# Sheet1.net
KiCad netlist of a schematic drawn in Altium Designer
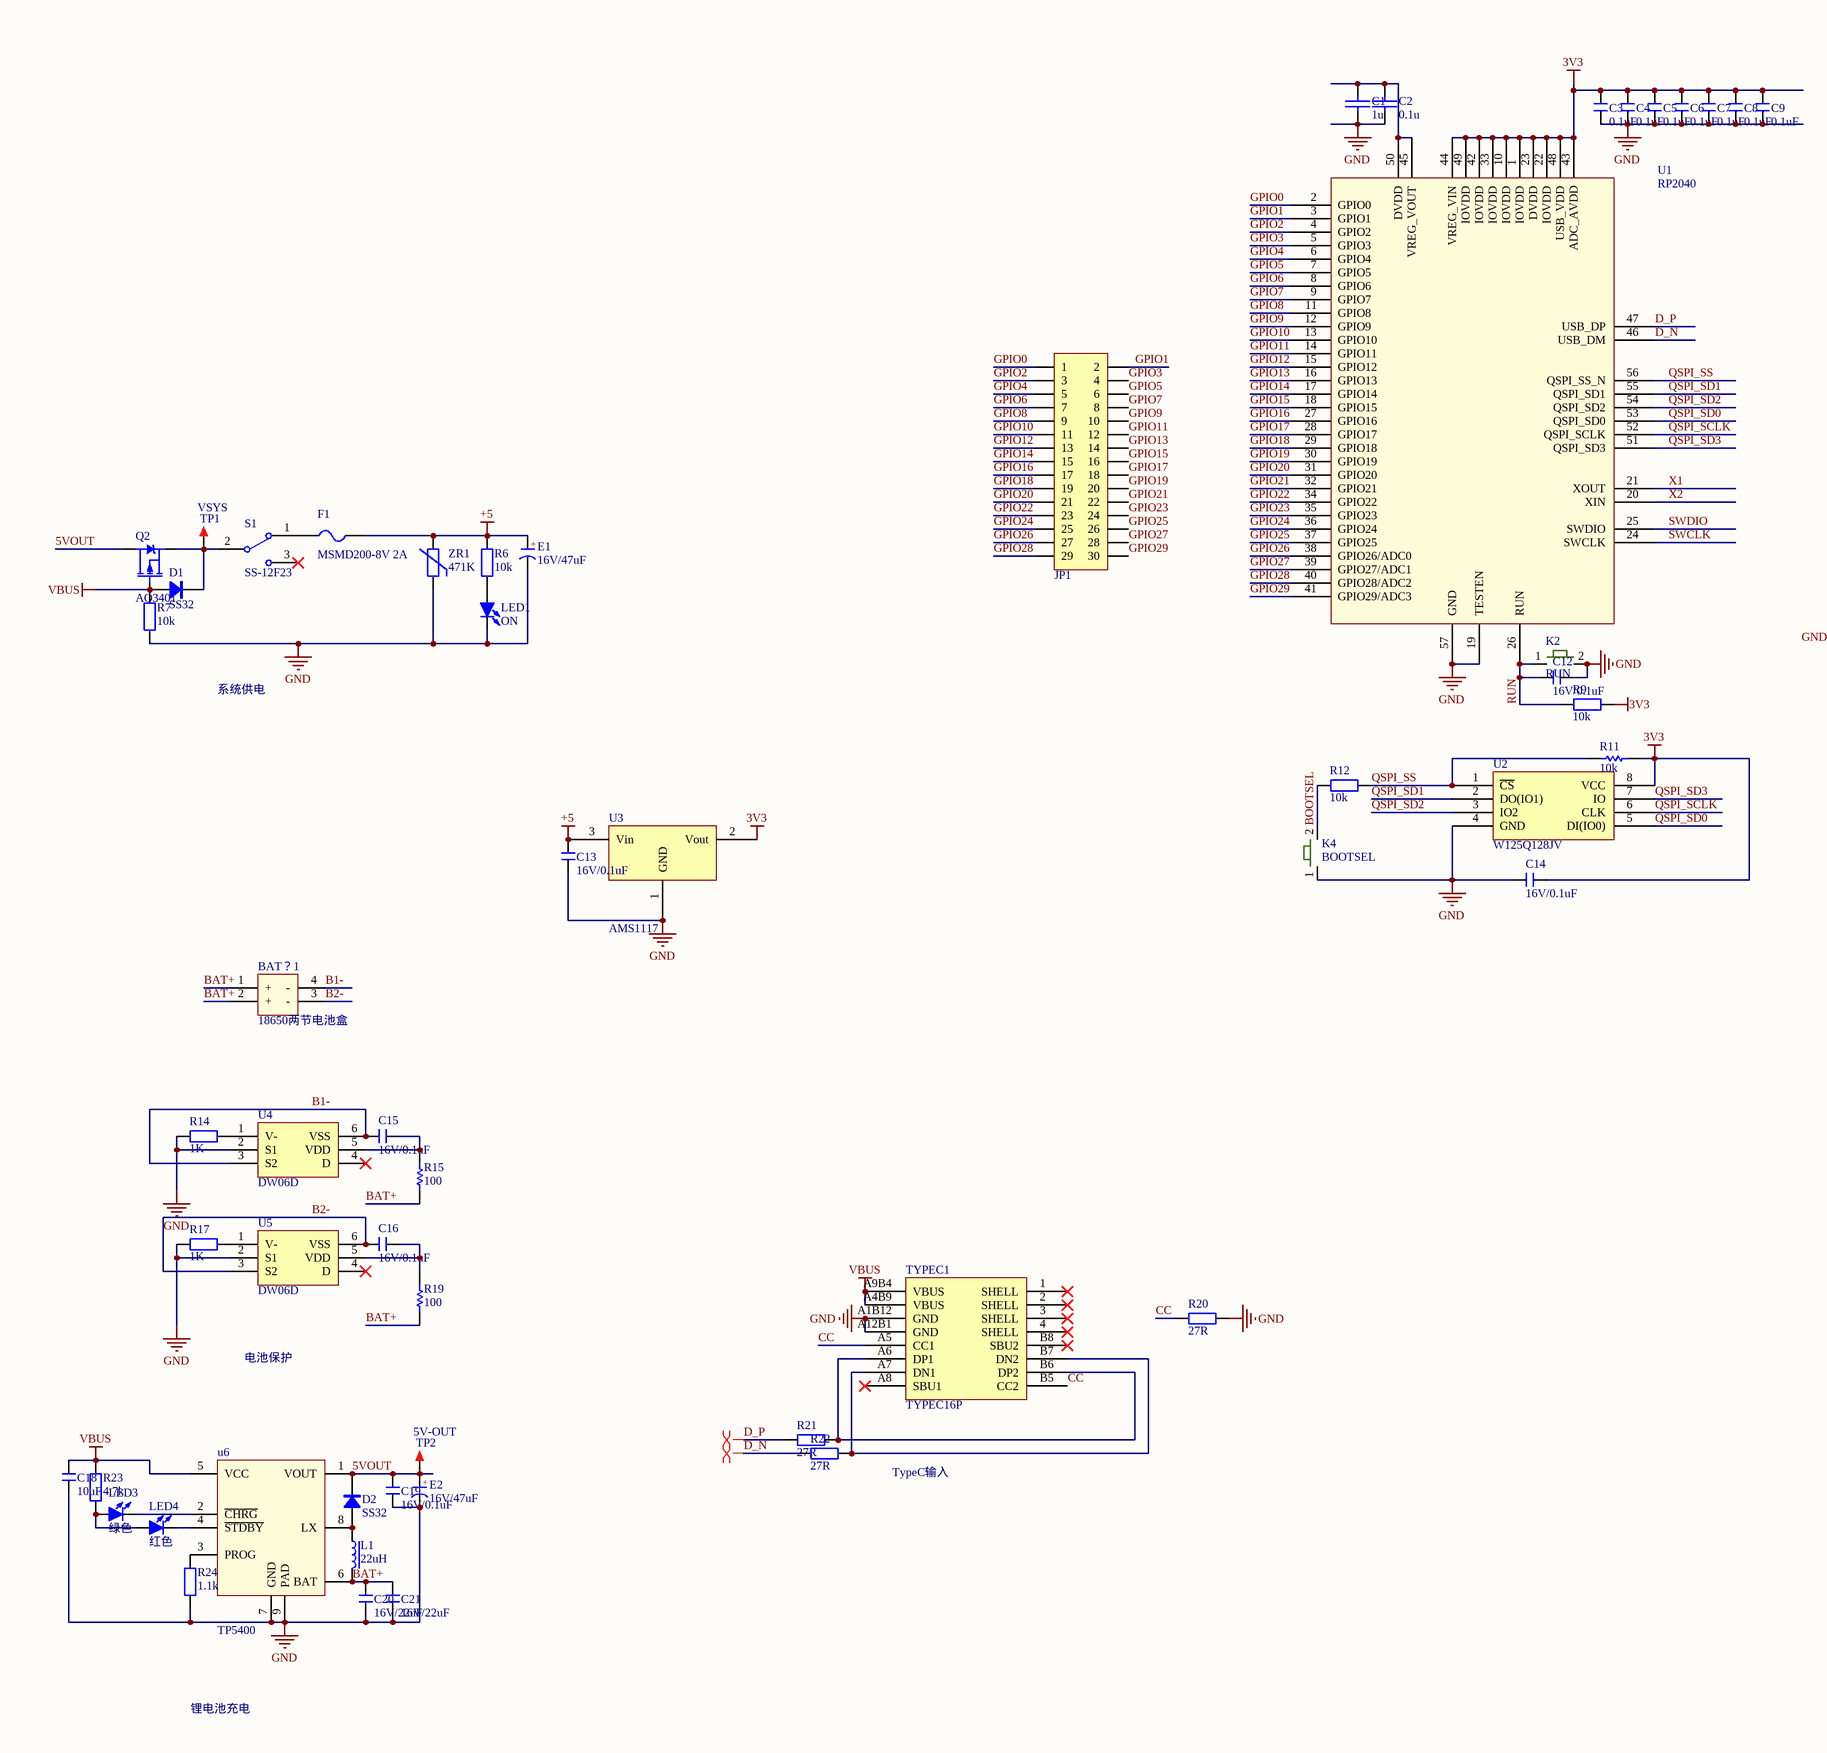
[diagram p0: Sheet1.SchDoc, left]
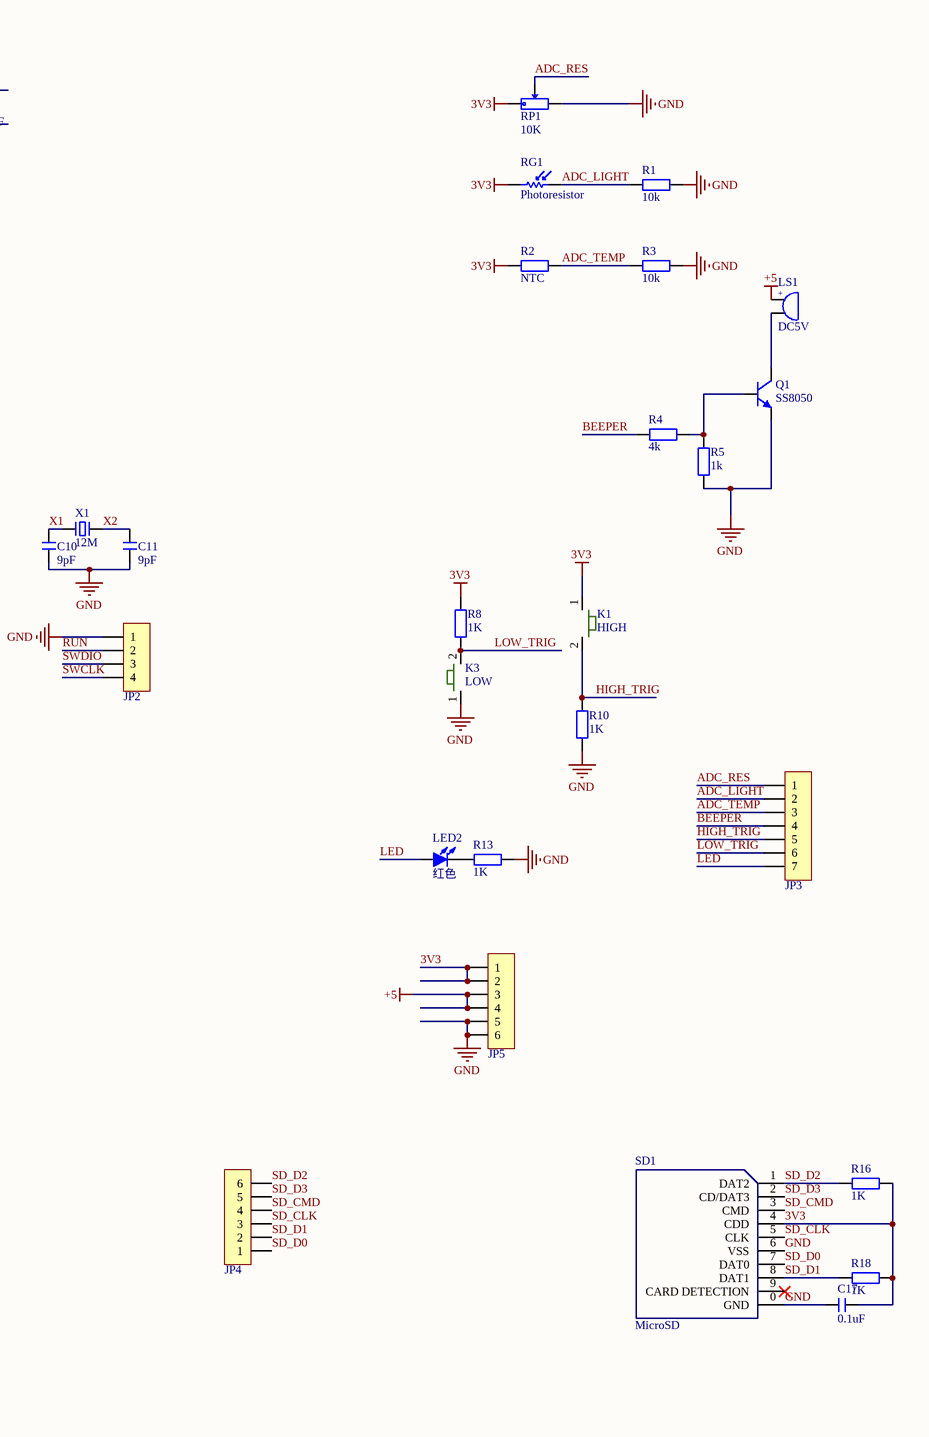
[diagram p1: Sheet1.SchDoc, right]

(export (version "E")
  (design (tool "Eeschema 10.0.6"))
  (components
    (comp (ref "BAT？1")
      (value "18650两节电池盒")
      (footprint "18650两节电池盒")
      (libsource (lib "Schlib1") (part "18650两节电池盒"))
    )
    (comp (ref "C1")
      (value "1u")
      (footprint "C 0603_L")
      (description "靠近RP2040")
      (libsource (lib "电容") (part "CAP"))
    )
    (comp (ref "C2")
      (value "0.1u")
      (footprint "C 0603_L")
      (description "无极性电容")
      (libsource (lib "电容") (part "CAP"))
    )
    (comp (ref "C3")
      (value "0.1uF")
      (footprint "C 0603_L")
      (description "无极性贴片电容")
      (fields (field (name "版权归属") "源创客"))
      (libsource (lib "3.1   - 电阻-电容-电感") (part "C"))
    )
    (comp (ref "C4")
      (value "0.1uF")
      (footprint "C 0603_L")
      (description "无极性贴片电容")
      (fields (field (name "版权归属") "源创客"))
      (libsource (lib "3.1   - 电阻-电容-电感") (part "C"))
    )
    (comp (ref "C5")
      (value "0.1uF")
      (footprint "C 0603_L")
      (description "无极性贴片电容")
      (fields (field (name "版权归属") "源创客"))
      (libsource (lib "3.1   - 电阻-电容-电感") (part "C"))
    )
    (comp (ref "C6")
      (value "0.1uF")
      (footprint "C 0603_L")
      (description "无极性贴片电容")
      (fields (field (name "版权归属") "源创客"))
      (libsource (lib "3.1   - 电阻-电容-电感") (part "C"))
    )
    (comp (ref "C7")
      (value "0.1uF")
      (footprint "C 0603_L")
      (description "无极性贴片电容")
      (fields (field (name "版权归属") "源创客"))
      (libsource (lib "3.1   - 电阻-电容-电感") (part "C"))
    )
    (comp (ref "C8")
      (value "0.1uF")
      (footprint "C 0603_L")
      (description "无极性贴片电容")
      (fields (field (name "版权归属") "源创客"))
      (libsource (lib "3.1   - 电阻-电容-电感") (part "C"))
    )
    (comp (ref "C9")
      (value "0.1uF")
      (footprint "C 0603_L")
      (description "无极性贴片电容")
      (fields (field (name "版权归属") "源创客"))
      (libsource (lib "3.1   - 电阻-电容-电感") (part "C"))
    )
    (comp (ref "C10")
      (value "9pF")
      (footprint "C 0603_L")
      (description "无极性贴片电容")
      (fields (field (name "版权归属") "源创客"))
      (libsource (lib "3.1   - 电阻-电容-电感") (part "C"))
    )
    (comp (ref "C11")
      (value "9pF")
      (footprint "C 0603_L")
      (description "无极性贴片电容")
      (fields (field (name "版权归属") "源创客"))
      (libsource (lib "3.1   - 电阻-电容-电感") (part "C"))
    )
    (comp (ref "C12")
      (value "16V/0.1uF")
      (footprint "C 0603_L")
      (description "无极性贴片电容")
      (fields (field (name "版权归属") "源创客"))
      (libsource (lib "3.1   - 电阻-电容-电感") (part "C"))
    )
    (comp (ref "C13")
      (value "16V/0.1uF")
      (footprint "C 0603_L")
      (description "无极性贴片电容")
      (fields (field (name "版权归属") "源创客"))
      (libsource (lib "3.1   - 电阻-电容-电感") (part "C"))
    )
    (comp (ref "C14")
      (value "16V/0.1uF")
      (footprint "C 0603_L")
      (description "无极性贴片电容")
      (fields (field (name "版权归属") "源创客"))
      (libsource (lib "3.1   - 电阻-电容-电感") (part "C"))
    )
    (comp (ref "C15")
      (value "16V/0.1uF")
      (footprint "C 0603_L")
      (description "无极性贴片电容")
      (fields (field (name "版权归属") "源创客"))
      (libsource (lib "3.1   - 电阻-电容-电感") (part "C"))
    )
    (comp (ref "C16")
      (value "16V/0.1uF")
      (footprint "C 0603_L")
      (description "无极性贴片电容")
      (fields (field (name "版权归属") "源创客"))
      (libsource (lib "3.1   - 电阻-电容-电感") (part "C"))
    )
    (comp (ref "C17")
      (value "0.1uF")
      (footprint "C 0603_L")
      (description "无极性贴片电容")
      (fields (field (name "版权归属") "源创客"))
      (libsource (lib "3.1   - 电阻-电容-电感") (part "C"))
    )
    (comp (ref "C18")
      (value "10uF")
      (footprint "C 0603_L")
      (description "无极性贴片电容")
      (fields (field (name "版权归属") "源创客"))
      (libsource (lib "3.1   - 电阻-电容-电感") (part "C"))
    )
    (comp (ref "C19")
      (value "16V/0.1uF")
      (footprint "C 0603_L")
      (description "无极性贴片电容")
      (fields (field (name "版权归属") "源创客"))
      (libsource (lib "3.1   - 电阻-电容-电感") (part "C"))
    )
    (comp (ref "C20")
      (value "16V/22uF")
      (footprint "C 0603_L")
      (description "无极性贴片电容")
      (fields (field (name "版权归属") "源创客"))
      (libsource (lib "3.1   - 电阻-电容-电感") (part "C"))
    )
    (comp (ref "C21")
      (value "16V/22uF")
      (footprint "C 0603_L")
      (description "无极性贴片电容")
      (fields (field (name "版权归属") "源创客"))
      (libsource (lib "3.1   - 电阻-电容-电感") (part "C"))
    )
    (comp (ref "D1")
      (value "SS32")
      (footprint "SMA")
      (description "肖特基二极管")
      (fields (field (name "版权归属") "源创客"))
      (libsource (lib "8.1   - 二极管-整流桥") (part "SS210"))
    )
    (comp (ref "D2")
      (value "SS32")
      (footprint "SMA")
      (description "肖特基二极管")
      (fields (field (name "版权归属") "源创客"))
      (libsource (lib "8.1   - 二极管-整流桥") (part "SS210"))
    )
    (comp (ref "E1")
      (value "16V/47uF")
      (footprint "CM C(5*5.4)")
      (description "贴片电解电容")
      (fields (field (name "版权归属") "源创客"))
      (libsource (lib "3.1   - 电阻-电容-电感") (part "C-CM"))
    )
    (comp (ref "E2")
      (value "16V/47uF")
      (footprint "CM C(5*5.4)")
      (description "贴片电解电容")
      (fields (field (name "版权归属") "源创客"))
      (libsource (lib "3.1   - 电阻-电容-电感") (part "C-CM"))
    )
    (comp (ref "F1")
      (value "MSMD200-8V 2A")
      (footprint "FU 1206")
      (description "贴片保险丝")
      (fields (field (name "版权归属") "源创客"))
      (libsource (lib "10.1 - 保险丝-晶振") (part "FU"))
    )
    (comp (ref "JP1")
      (value "Header 2X11")
      (footprint "HDR2.54-LI-2x15P")
      (description "15*2P接插件")
      (fields (field (name "版权归属") "源创客"))
      (libsource (lib "4.6   - 接插件-脚距2.54") (part "Header 15X2"))
    )
    (comp (ref "JP2")
      (value "DEBUG")
      (footprint "HDR2.54-LI-4P")
      (description "4P接插件")
      (fields (field (name "版权归属") "源创客"))
      (libsource (lib "4.6   - 接插件-脚距2.54") (part "Header 4"))
    )
    (comp (ref "JP3")
      (value "HDR-1X7")
      (footprint "HDR2.54-LI-7P")
      (description "7P接插件")
      (fields (field (name "版权归属") "源创客"))
      (libsource (lib "4.6   - 接插件-脚距2.54") (part "Header 7"))
    )
    (comp (ref "JP4")
      (value "HDR-1X6")
      (footprint "HDR2.54-LI-6P")
      (description "6P接插件")
      (fields (field (name "版权归属") "源创客"))
      (libsource (lib "") (part "Header 6_1"))
    )
    (comp (ref "JP5")
      (value "HDR-1X6")
      (footprint "HDR2.54-LI-6P")
      (description "6P接插件")
      (fields (field (name "版权归属") "源创客"))
      (libsource (lib "4.6   - 接插件-脚距2.54") (part "Header 6"))
    )
    (comp (ref "K1") (value "HIGH") (footprint "轻触按键") (libsource (lib "Schlib1") (part "两脚轻触开关")))
    (comp (ref "K2") (value "RUN") (footprint "轻触按键") (libsource (lib "Schlib1") (part "两脚轻触开关")))
    (comp (ref "K3") (value "LOW") (footprint "轻触按键") (libsource (lib "Schlib1") (part "两脚轻触开关")))
    (comp (ref "K4") (value "BOOTSEL") (footprint "轻触按键") (libsource (lib "Schlib1") (part "两脚轻触开关")))
    (comp (ref "L1")
      (value "22uH")
      (footprint "NR4020")
      (description "NR磁胶电感")
      (fields (field (name "版权归属") "源创客"))
      (libsource (lib "3.1   - 电阻-电容-电感") (part "L-NR"))
    )
    (comp (ref "LED1")
      (value "ON")
      (footprint "LED 0603R")
      (description "贴片LED")
      (fields (field (name "版权归属") "源创客"))
      (libsource (lib "9.1   - LED") (part "LED-SMD"))
    )
    (comp (ref "LED2")
      (value "红色")
      (footprint "LED 0603R")
      (description "贴片LED")
      (fields (field (name "版权归属") "源创客"))
      (libsource (lib "9.1   - LED") (part "LED-SMD"))
    )
    (comp (ref "LED3")
      (value "绿色")
      (footprint "LED 0603G")
      (description "贴片LED")
      (fields (field (name "版权归属") "源创客"))
      (libsource (lib "9.1   - LED") (part "LED-SMD"))
    )
    (comp (ref "LED4")
      (value "红色")
      (footprint "LED 0603R")
      (description "贴片LED")
      (fields (field (name "版权归属") "源创客"))
      (libsource (lib "9.1   - LED") (part "LED-SMD"))
    )
    (comp (ref "LS1")
      (value "DC5V")
      (footprint "BUZZER-7525")
      (description "蜂鸣器")
      (fields (field (name "版权归属") "源创客"))
      (libsource (lib "15.1 - 未分类器件") (part "BEEP"))
    )
    (comp (ref "Q1")
      (value "SS8050")
      (footprint "SOT-23")
      (description "高频放大-NPN型")
      (fields (field (name "版权归属") "源创客"))
      (libsource (lib "6.2   - 三极管") (part "8050-SMD"))
    )
    (comp (ref "Q2")
      (value "AO3401")
      (footprint "SOT23")
      (description "P沟道场效应管")
      (libsource (lib "MOS管") (part "P-MOS"))
    )
    (comp (ref "R1")
      (value "10k")
      (footprint "R 0603_L")
      (description "贴片电阻")
      (fields (field (name "版权归属") "源创客"))
      (libsource (lib "3.1   - 电阻-电容-电感") (part "R"))
    )
    (comp (ref "R2")
      (value "NTC")
      (footprint "R 0603_L")
      (description "贴片电阻")
      (fields (field (name "版权归属") "源创客"))
      (libsource (lib "3.1   - 电阻-电容-电感") (part "R"))
    )
    (comp (ref "R3")
      (value "10k")
      (footprint "R 0603_L")
      (description "贴片电阻")
      (fields (field (name "版权归属") "源创客"))
      (libsource (lib "3.1   - 电阻-电容-电感") (part "R"))
    )
    (comp (ref "R4")
      (value "4k")
      (footprint "R 0603_L")
      (description "贴片电阻")
      (fields (field (name "版权归属") "源创客"))
      (libsource (lib "3.1   - 电阻-电容-电感") (part "R"))
    )
    (comp (ref "R5")
      (value "1k")
      (footprint "R 0603_L")
      (description "贴片电阻")
      (fields (field (name "版权归属") "源创客"))
      (libsource (lib "3.1   - 电阻-电容-电感") (part "R"))
    )
    (comp (ref "R6")
      (value "10k")
      (footprint "R 0603_L")
      (description "贴片电阻")
      (fields (field (name "版权归属") "源创客"))
      (libsource (lib "3.1   - 电阻-电容-电感") (part "R"))
    )
    (comp (ref "R7")
      (value "10k")
      (footprint "R 0603_L")
      (description "贴片电阻")
      (fields (field (name "版权归属") "源创客"))
      (libsource (lib "3.1   - 电阻-电容-电感") (part "R"))
    )
    (comp (ref "R8")
      (value "1K")
      (footprint "R 0603_L")
      (description "贴片电阻")
      (fields (field (name "版权归属") "源创客"))
      (libsource (lib "3.1   - 电阻-电容-电感") (part "R"))
    )
    (comp (ref "R9")
      (value "10k")
      (footprint "R 0603_L")
      (description "贴片电阻")
      (fields (field (name "版权归属") "源创客"))
      (libsource (lib "3.1   - 电阻-电容-电感") (part "R"))
    )
    (comp (ref "R10")
      (value "1K")
      (footprint "R 0603_L")
      (description "贴片电阻")
      (fields (field (name "版权归属") "源创客"))
      (libsource (lib "3.1   - 电阻-电容-电感") (part "R"))
    )
    (comp (ref "R11") (value "10k") (footprint "R 0603_L") (libsource (lib "电阻") (part "RES")))
    (comp (ref "R12")
      (value "10k")
      (footprint "R 0603_L")
      (description "贴片电阻")
      (fields (field (name "版权归属") "源创客"))
      (libsource (lib "3.1   - 电阻-电容-电感") (part "R"))
    )
    (comp (ref "R13")
      (value "1K")
      (footprint "R 0603_L")
      (description "贴片电阻")
      (fields (field (name "版权归属") "源创客"))
      (libsource (lib "3.1   - 电阻-电容-电感") (part "R"))
    )
    (comp (ref "R14")
      (value "1K")
      (footprint "R 0603_L")
      (description "贴片电阻")
      (fields (field (name "版权归属") "源创客"))
      (libsource (lib "3.1   - 电阻-电容-电感") (part "R"))
    )
    (comp (ref "R15") (value "100") (footprint "R 0603_L") (libsource (lib "电阻") (part "RES")))
    (comp (ref "R16")
      (value "1K")
      (footprint "R 0603_L")
      (description "贴片电阻")
      (fields (field (name "版权归属") "源创客"))
      (libsource (lib "3.1   - 电阻-电容-电感") (part "R"))
    )
    (comp (ref "R17")
      (value "1K")
      (footprint "R 0603_L")
      (description "贴片电阻")
      (fields (field (name "版权归属") "源创客"))
      (libsource (lib "3.1   - 电阻-电容-电感") (part "R"))
    )
    (comp (ref "R18")
      (value "1K")
      (footprint "R 0603_L")
      (description "贴片电阻")
      (fields (field (name "版权归属") "源创客"))
      (libsource (lib "3.1   - 电阻-电容-电感") (part "R"))
    )
    (comp (ref "R19") (value "100") (footprint "R 0603_L") (libsource (lib "电阻") (part "RES")))
    (comp (ref "R20")
      (value "27R")
      (footprint "R 0603_L")
      (description "贴片电阻")
      (fields (field (name "版权归属") "源创客"))
      (libsource (lib "3.1   - 电阻-电容-电感") (part "R"))
    )
    (comp (ref "R21")
      (value "27R")
      (footprint "R 0603_L")
      (description "贴片电阻")
      (fields (field (name "版权归属") "源创客"))
      (libsource (lib "3.1   - 电阻-电容-电感") (part "R"))
    )
    (comp (ref "R22")
      (value "27R")
      (footprint "R 0603_L")
      (description "贴片电阻")
      (fields (field (name "版权归属") "源创客"))
      (libsource (lib "3.1   - 电阻-电容-电感") (part "R"))
    )
    (comp (ref "R23")
      (value "4.7k")
      (footprint "R 0603_L")
      (description "贴片电阻")
      (fields (field (name "版权归属") "源创客"))
      (libsource (lib "3.1   - 电阻-电容-电感") (part "R"))
    )
    (comp (ref "R24")
      (value "1.1k")
      (footprint "R 0603_L")
      (description "贴片电阻")
      (fields (field (name "版权归属") "源创客"))
      (libsource (lib "3.1   - 电阻-电容-电感") (part "R"))
    )
    (comp (ref "RG1")
      (value "Photoresistor")
      (footprint "Photoresistor")
      (description "光敏电阻")
      (libsource (lib "电阻") (part "Photoresistor"))
    )
    (comp (ref "RP1")
      (value "10K")
      (footprint "拨盘电位器")
      (description "贴片电位器")
      (fields (field (name "版权归属") "源创客"))
      (libsource (lib "3.1   - 电阻-电容-电感") (part "RP-SMD"))
    )
    (comp (ref "S1")
      (value "SS-12F23")
      (footprint "SK-12D07VG3")
      (description "1路波动开关")
      (fields (field (name "版权归属") "源创客"))
      (libsource (lib "5.1   - 按键-开关") (part "SSW-1P"))
    )
    (comp (ref "SD1") (value "MicroSD") (footprint "Micro SD") (libsource (lib "SD Card") (part "MicroSD")))
    (comp (ref "TP1")
      (value "VSYS")
      (footprint "TEST 1")
      (description "测试点")
      (fields (field (name "版权归属") "源创客"))
      (libsource (lib "15.1 - 未分类器件") (part "TEST"))
    )
    (comp (ref "TP2")
      (value "5V-OUT")
      (footprint "TEST 1")
      (description "测试点")
      (fields (field (name "版权归属") "源创客"))
      (libsource (lib "15.1 - 未分类器件") (part "TEST"))
    )
    (comp (ref "TYPEC1")
      (value "TYPEC16P")
      (footprint "TYPEC-16P")
      (libsource (lib "Schlib1") (part "TYPEC16P"))
    )
    (comp (ref "U1") (value "RP2040") (footprint "QFN-56") (libsource (lib "Schlib1") (part "RP2040")))
    (comp (ref "U2")
      (value "W125Q128JV")
      (footprint "SOIC-8-208mil")
      (libsource (lib "Schlib1") (part "W125Q128JV"))
    )
    (comp (ref "U3")
      (value "AMS1117")
      (footprint "SOT89")
      (description "三端稳压芯片")
      (libsource (lib "电源芯片") (part "AMS1117"))
    )
    (comp (ref "U4") (value "DW06D") (footprint "SOT23-6") (libsource (lib "Schlib1") (part "DW06D")))
    (comp (ref "U5") (value "DW06D") (footprint "SOT23-6") (libsource (lib "Schlib1") (part "DW06D")))
    (comp (ref "u6") (value "TP5400") (footprint "ESOP8") (libsource (lib "Schlib1") (part "TP5400")))
    (comp (ref "X1")
      (value "12M")
      (footprint "OSC HC-49SMD")
      (description "2脚无源脚晶振")
      (libsource (lib "晶振") (part "XTAL-2P"))
    )
    (comp (ref "ZR1")
      (value "471K")
      (footprint "R 0603_L")
      (description "压敏电阻")
      (fields (field (name "版权归属") "源创客"))
      (libsource (lib "3.1   - 电阻-电容-电感") (part "R_VDR"))
    )
  )
  (nets
    (net (code "1") (name "+5") (class "Default")
      (node (ref "C13") (pin "2") (pinfunction "2_2") (pintype "passive"))
      (node (ref "E1") (pin "1") (pinfunction "A_1") (pintype "passive"))
      (node (ref "F1") (pin "2") (pinfunction "2_2") (pintype "passive"))
      (node (ref "JP5") (pin "3") (pinfunction "3_3") (pintype "passive"))
      (node (ref "JP5") (pin "4") (pinfunction "4_4") (pintype "passive"))
      (node (ref "LS1") (pin "1") (pinfunction "1_1") (pintype "passive"))
      (node (ref "R6") (pin "2") (pinfunction "2_2") (pintype "passive"))
      (node (ref "U3") (pin "3") (pinfunction "Vin_3") (pintype "passive"))
      (node (ref "ZR1") (pin "2") (pinfunction "2_2") (pintype "passive"))
    )
    (net (code "2") (name "/5VOUT") (class "Default")
      (node (ref "C19") (pin "2") (pinfunction "2_2") (pintype "passive"))
      (node (ref "D2") (pin "2") (pinfunction "K_2") (pintype "passive"))
      (node (ref "E2") (pin "1") (pinfunction "A_1") (pintype "passive"))
      (node (ref "Q2") (pin "D") (pinfunction "D_D") (pintype "passive"))
      (node (ref "TP2") (pin "1") (pinfunction "1_1") (pintype "passive"))
      (node (ref "u6") (pin "1") (pinfunction "VOUT_1") (pintype "passive"))
    )
    (net (code "3") (name "/ADC_LIGHT") (class "Default")
      (node (ref "JP3") (pin "2") (pinfunction "2_2") (pintype "passive"))
      (node (ref "R1") (pin "2") (pinfunction "2_2") (pintype "passive"))
      (node (ref "RG1") (pin "2") (pinfunction "2_2") (pintype "passive"))
    )
    (net (code "4") (name "/ADC_RES") (class "Default")
      (node (ref "JP3") (pin "1") (pinfunction "1_1") (pintype "passive"))
      (node (ref "RP1") (pin "2") (pinfunction "2_2") (pintype "passive"))
    )
    (net (code "5") (name "/ADC_TEMP") (class "Default")
      (node (ref "JP3") (pin "3") (pinfunction "3_3") (pintype "passive"))
      (node (ref "R2") (pin "2") (pinfunction "2_2") (pintype "passive"))
      (node (ref "R3") (pin "2") (pinfunction "2_2") (pintype "passive"))
    )
    (net (code "6") (name "/B1-") (class "Default")
      (node (ref "BAT？1") (pin "4") (pinfunction "-_4") (pintype "passive"))
      (node (ref "C15") (pin "2") (pinfunction "2_2") (pintype "passive"))
      (node (ref "U4") (pin "3") (pinfunction "S2_3") (pintype "passive"))
      (node (ref "U4") (pin "6") (pinfunction "VSS_6") (pintype "passive"))
    )
    (net (code "7") (name "/B2-") (class "Default")
      (node (ref "BAT？1") (pin "3") (pinfunction "-_3") (pintype "passive"))
      (node (ref "C16") (pin "2") (pinfunction "2_2") (pintype "passive"))
      (node (ref "U5") (pin "3") (pinfunction "S2_3") (pintype "passive"))
      (node (ref "U5") (pin "6") (pinfunction "VSS_6") (pintype "passive"))
    )
    (net (code "8") (name "/BAT+") (class "Default")
      (node (ref "BAT？1") (pin "1") (pinfunction "+_1") (pintype "passive"))
      (node (ref "BAT？1") (pin "2") (pinfunction "+_2") (pintype "passive"))
      (node (ref "C20") (pin "2") (pinfunction "2_2") (pintype "passive"))
      (node (ref "C21") (pin "2") (pinfunction "2_2") (pintype "passive"))
      (node (ref "L1") (pin "2") (pinfunction "2_2") (pintype "passive"))
      (node (ref "R15") (pin "2") (pinfunction "2_2") (pintype "passive"))
      (node (ref "R19") (pin "2") (pinfunction "2_2") (pintype "passive"))
      (node (ref "u6") (pin "6") (pinfunction "BAT_6") (pintype "passive"))
    )
    (net (code "9") (name "/BEEPER") (class "Default")
      (node (ref "JP3") (pin "4") (pinfunction "4_4") (pintype "passive"))
      (node (ref "R4") (pin "1") (pinfunction "1_1") (pintype "passive"))
    )
    (net (code "10") (name "/BOOTSEL") (class "Default")
      (node (ref "K4") (pin "2") (pintype "passive"))
      (node (ref "R12") (pin "2") (pinfunction "2_2") (pintype "passive"))
    )
    (net (code "11") (name "/CC") (class "Default")
      (node (ref "R20") (pin "1") (pinfunction "1_1") (pintype "passive"))
      (node (ref "TYPEC1") (pin "A5") (pinfunction "CC1_A5") (pintype "passive"))
      (node (ref "TYPEC1") (pin "B5") (pinfunction "CC2_B5") (pintype "passive"))
    )
    (net (code "12") (name "/D_N") (class "Default")
      (node (ref "R22") (pin "1") (pinfunction "1_1") (pintype "passive"))
      (node (ref "U1") (pin "46") (pinfunction "USB_DM_46") (pintype "passive"))
    )
    (net (code "13") (name "/D_P") (class "Default")
      (node (ref "R21") (pin "1") (pinfunction "1_1") (pintype "passive"))
      (node (ref "U1") (pin "47") (pinfunction "USB_DP_47") (pintype "passive"))
    )
    (net (code "14") (name "/GPIO0") (class "Default")
      (node (ref "JP1") (pin "1") (pinfunction "1_1") (pintype "passive"))
      (node (ref "U1") (pin "2") (pinfunction "GPIO0_2") (pintype "passive"))
    )
    (net (code "15") (name "/GPIO1") (class "Default")
      (node (ref "JP1") (pin "2") (pinfunction "2_2") (pintype "passive"))
      (node (ref "U1") (pin "3") (pinfunction "GPIO1_3") (pintype "passive"))
    )
    (net (code "16") (name "/GPIO2") (class "Default")
      (node (ref "JP1") (pin "3") (pinfunction "3_3") (pintype "passive"))
      (node (ref "U1") (pin "4") (pinfunction "GPIO2_4") (pintype "passive"))
    )
    (net (code "17") (name "/GPIO3") (class "Default")
      (node (ref "JP1") (pin "4") (pinfunction "4_4") (pintype "passive"))
      (node (ref "U1") (pin "5") (pinfunction "GPIO3_5") (pintype "passive"))
    )
    (net (code "18") (name "/GPIO4") (class "Default")
      (node (ref "JP1") (pin "5") (pinfunction "5_5") (pintype "passive"))
      (node (ref "U1") (pin "6") (pinfunction "GPIO4_6") (pintype "passive"))
    )
    (net (code "19") (name "/GPIO5") (class "Default")
      (node (ref "JP1") (pin "6") (pinfunction "6_6") (pintype "passive"))
      (node (ref "U1") (pin "7") (pinfunction "GPIO5_7") (pintype "passive"))
    )
    (net (code "20") (name "/GPIO6") (class "Default")
      (node (ref "JP1") (pin "7") (pinfunction "7_7") (pintype "passive"))
      (node (ref "U1") (pin "8") (pinfunction "GPIO6_8") (pintype "passive"))
    )
    (net (code "21") (name "/GPIO7") (class "Default")
      (node (ref "JP1") (pin "8") (pinfunction "8_8") (pintype "passive"))
      (node (ref "U1") (pin "9") (pinfunction "GPIO7_9") (pintype "passive"))
    )
    (net (code "22") (name "/GPIO8") (class "Default")
      (node (ref "JP1") (pin "9") (pinfunction "9_9") (pintype "passive"))
      (node (ref "U1") (pin "11") (pinfunction "GPIO8_11") (pintype "passive"))
    )
    (net (code "23") (name "/GPIO9") (class "Default")
      (node (ref "JP1") (pin "10") (pinfunction "10_10") (pintype "passive"))
      (node (ref "U1") (pin "12") (pinfunction "GPIO9_12") (pintype "passive"))
    )
    (net (code "24") (name "/GPIO10") (class "Default")
      (node (ref "JP1") (pin "11") (pinfunction "11_11") (pintype "passive"))
      (node (ref "U1") (pin "13") (pinfunction "GPIO10_13") (pintype "passive"))
    )
    (net (code "25") (name "/GPIO11") (class "Default")
      (node (ref "JP1") (pin "12") (pinfunction "12_12") (pintype "passive"))
      (node (ref "U1") (pin "14") (pinfunction "GPIO11_14") (pintype "passive"))
    )
    (net (code "26") (name "/GPIO12") (class "Default")
      (node (ref "JP1") (pin "13") (pinfunction "13_13") (pintype "passive"))
      (node (ref "U1") (pin "15") (pinfunction "GPIO12_15") (pintype "passive"))
    )
    (net (code "27") (name "/GPIO13") (class "Default")
      (node (ref "JP1") (pin "14") (pinfunction "14_14") (pintype "passive"))
      (node (ref "U1") (pin "16") (pinfunction "GPIO13_16") (pintype "passive"))
    )
    (net (code "28") (name "/GPIO14") (class "Default")
      (node (ref "JP1") (pin "15") (pinfunction "15_15") (pintype "passive"))
      (node (ref "U1") (pin "17") (pinfunction "GPIO14_17") (pintype "passive"))
    )
    (net (code "29") (name "/GPIO15") (class "Default")
      (node (ref "JP1") (pin "16") (pinfunction "16_16") (pintype "passive"))
      (node (ref "U1") (pin "18") (pinfunction "GPIO15_18") (pintype "passive"))
    )
    (net (code "30") (name "/GPIO16") (class "Default")
      (node (ref "JP1") (pin "17") (pinfunction "17_17") (pintype "passive"))
      (node (ref "U1") (pin "27") (pinfunction "GPIO16_27") (pintype "passive"))
    )
    (net (code "31") (name "/GPIO17") (class "Default")
      (node (ref "JP1") (pin "18") (pinfunction "18_18") (pintype "passive"))
      (node (ref "U1") (pin "28") (pinfunction "GPIO17_28") (pintype "passive"))
    )
    (net (code "32") (name "/GPIO18") (class "Default")
      (node (ref "JP1") (pin "19") (pinfunction "19_19") (pintype "passive"))
      (node (ref "U1") (pin "29") (pinfunction "GPIO18_29") (pintype "passive"))
    )
    (net (code "33") (name "/GPIO19") (class "Default")
      (node (ref "JP1") (pin "20") (pinfunction "20_20") (pintype "passive"))
      (node (ref "U1") (pin "30") (pinfunction "GPIO19_30") (pintype "passive"))
    )
    (net (code "34") (name "/GPIO20") (class "Default")
      (node (ref "JP1") (pin "21") (pinfunction "21_21") (pintype "passive"))
      (node (ref "U1") (pin "31") (pinfunction "GPIO20_31") (pintype "passive"))
    )
    (net (code "35") (name "/GPIO21") (class "Default")
      (node (ref "JP1") (pin "22") (pinfunction "22_22") (pintype "passive"))
      (node (ref "U1") (pin "32") (pinfunction "GPIO21_32") (pintype "passive"))
    )
    (net (code "36") (name "/GPIO22") (class "Default")
      (node (ref "JP1") (pin "23") (pinfunction "23_23") (pintype "passive"))
      (node (ref "U1") (pin "34") (pinfunction "GPIO22_34") (pintype "passive"))
    )
    (net (code "37") (name "/GPIO23") (class "Default")
      (node (ref "JP1") (pin "24") (pinfunction "24_24") (pintype "passive"))
      (node (ref "U1") (pin "35") (pinfunction "GPIO23_35") (pintype "passive"))
    )
    (net (code "38") (name "/GPIO24") (class "Default")
      (node (ref "JP1") (pin "25") (pinfunction "25_25") (pintype "passive"))
      (node (ref "U1") (pin "36") (pinfunction "GPIO24_36") (pintype "passive"))
    )
    (net (code "39") (name "/GPIO25") (class "Default")
      (node (ref "JP1") (pin "26") (pinfunction "26_26") (pintype "passive"))
      (node (ref "U1") (pin "37") (pinfunction "GPIO25_37") (pintype "passive"))
    )
    (net (code "40") (name "/GPIO26") (class "Default")
      (node (ref "JP1") (pin "27") (pinfunction "27_27") (pintype "passive"))
      (node (ref "U1") (pin "38") (pinfunction "GPIO26/ADC0_38") (pintype "passive"))
    )
    (net (code "41") (name "/GPIO27") (class "Default")
      (node (ref "JP1") (pin "28") (pinfunction "28_28") (pintype "passive"))
      (node (ref "U1") (pin "39") (pinfunction "GPIO27/ADC1_39") (pintype "passive"))
    )
    (net (code "42") (name "/GPIO28") (class "Default")
      (node (ref "JP1") (pin "29") (pinfunction "29_29") (pintype "passive"))
      (node (ref "U1") (pin "40") (pinfunction "GPIO28/ADC2_40") (pintype "passive"))
    )
    (net (code "43") (name "/GPIO29") (class "Default")
      (node (ref "JP1") (pin "30") (pinfunction "30_30") (pintype "passive"))
      (node (ref "U1") (pin "41") (pinfunction "GPIO29/ADC3_41") (pintype "passive"))
    )
    (net (code "44") (name "/HIGH_TRIG") (class "Default")
      (node (ref "JP3") (pin "5") (pinfunction "5_5") (pintype "passive"))
      (node (ref "K1") (pin "2") (pintype "passive"))
      (node (ref "R10") (pin "2") (pinfunction "2_2") (pintype "passive"))
    )
    (net (code "45") (name "/LED") (class "Default")
      (node (ref "JP3") (pin "7") (pinfunction "7_7") (pintype "passive"))
      (node (ref "LED2") (pin "1") (pinfunction "A_1") (pintype "passive"))
    )
    (net (code "46") (name "/LOW_TRIG") (class "Default")
      (node (ref "JP3") (pin "6") (pinfunction "6_6") (pintype "passive"))
      (node (ref "K3") (pin "2") (pintype "passive"))
      (node (ref "R8") (pin "1") (pinfunction "1_1") (pintype "passive"))
    )
    (net (code "47") (name "/QSPI_SCLK") (class "Default")
      (node (ref "U1") (pin "52") (pinfunction "QSPI_SCLK_52") (pintype "passive"))
      (node (ref "U2") (pin "6") (pinfunction "CLK_6") (pintype "passive"))
    )
    (net (code "48") (name "/QSPI_SD0") (class "Default")
      (node (ref "U1") (pin "53") (pinfunction "QSPI_SD0_53") (pintype "passive"))
      (node (ref "U2") (pin "5") (pinfunction "DI(IO0)_5") (pintype "passive"))
    )
    (net (code "49") (name "/QSPI_SD1") (class "Default")
      (node (ref "U1") (pin "55") (pinfunction "QSPI_SD1_55") (pintype "passive"))
      (node (ref "U2") (pin "2") (pinfunction "DO(IO1)_2") (pintype "passive"))
    )
    (net (code "50") (name "/QSPI_SD2") (class "Default")
      (node (ref "U1") (pin "54") (pinfunction "QSPI_SD2_54") (pintype "passive"))
      (node (ref "U2") (pin "3") (pinfunction "IO2_3") (pintype "passive"))
    )
    (net (code "51") (name "/QSPI_SD3") (class "Default")
      (node (ref "U1") (pin "51") (pinfunction "QSPI_SD3_51") (pintype "passive"))
      (node (ref "U2") (pin "7") (pinfunction "IO_7") (pintype "passive"))
    )
    (net (code "52") (name "/QSPI_SS") (class "Default")
      (node (ref "R11") (pin "1") (pinfunction "1_1") (pintype "passive"))
      (node (ref "R12") (pin "1") (pinfunction "1_1") (pintype "passive"))
      (node (ref "U1") (pin "56") (pinfunction "QSPI_SS_N_56") (pintype "passive"))
      (node (ref "U2") (pin "1") (pinfunction "~{CS}_1") (pintype "passive"))
    )
    (net (code "53") (name "/RUN") (class "Default")
      (node (ref "C12") (pin "2") (pinfunction "2_2") (pintype "passive"))
      (node (ref "JP2") (pin "2") (pinfunction "2_2") (pintype "passive"))
      (node (ref "K2") (pin "1") (pintype "passive"))
      (node (ref "R9") (pin "2") (pinfunction "2_2") (pintype "passive"))
      (node (ref "U1") (pin "26") (pinfunction "RUN_26") (pintype "passive"))
    )
    (net (code "54") (name "/SD_CLK") (class "Default")
      (node (ref "JP4") (pin "3") (pinfunction "3_3") (pintype "passive"))
      (node (ref "SD1") (pin "5") (pinfunction "CLK_5") (pintype "passive"))
    )
    (net (code "55") (name "/SD_CMD") (class "Default")
      (node (ref "JP4") (pin "4") (pinfunction "4_4") (pintype "passive"))
      (node (ref "SD1") (pin "3") (pinfunction "CMD_3") (pintype "passive"))
    )
    (net (code "56") (name "/SD_D0") (class "Default")
      (node (ref "JP4") (pin "1") (pinfunction "1_1") (pintype "passive"))
      (node (ref "SD1") (pin "7") (pinfunction "DAT0_7") (pintype "passive"))
    )
    (net (code "57") (name "/SD_D1") (class "Default")
      (node (ref "JP4") (pin "2") (pinfunction "2_2") (pintype "passive"))
      (node (ref "R18") (pin "1") (pinfunction "1_1") (pintype "passive"))
      (node (ref "SD1") (pin "8") (pinfunction "DAT1_8") (pintype "passive"))
    )
    (net (code "58") (name "/SD_D2") (class "Default")
      (node (ref "JP4") (pin "6") (pinfunction "6_6") (pintype "passive"))
      (node (ref "R16") (pin "1") (pinfunction "1_1") (pintype "passive"))
      (node (ref "SD1") (pin "1") (pinfunction "DAT2_1") (pintype "passive"))
    )
    (net (code "59") (name "/SD_D3") (class "Default")
      (node (ref "JP4") (pin "5") (pinfunction "5_5") (pintype "passive"))
      (node (ref "SD1") (pin "2") (pinfunction "CD/DAT3_2") (pintype "passive"))
    )
    (net (code "60") (name "/SWCLK") (class "Default")
      (node (ref "JP2") (pin "4") (pinfunction "4_4") (pintype "passive"))
      (node (ref "U1") (pin "24") (pinfunction "SWCLK_24") (pintype "passive"))
    )
    (net (code "61") (name "/SWDIO") (class "Default")
      (node (ref "JP2") (pin "3") (pinfunction "3_3") (pintype "passive"))
      (node (ref "U1") (pin "25") (pinfunction "SWDIO_25") (pintype "passive"))
    )
    (net (code "62") (name "/X1") (class "Default")
      (node (ref "C10") (pin "2") (pinfunction "2_2") (pintype "passive"))
      (node (ref "U1") (pin "21") (pinfunction "XOUT_21") (pintype "passive"))
      (node (ref "X1") (pin "1") (pinfunction "1_1") (pintype "passive"))
    )
    (net (code "63") (name "/X2") (class "Default")
      (node (ref "C11") (pin "2") (pinfunction "2_2") (pintype "passive"))
      (node (ref "U1") (pin "20") (pinfunction "XIN_20") (pintype "passive"))
      (node (ref "X1") (pin "2") (pinfunction "2_2") (pintype "passive"))
    )
    (net (code "64") (name "3V3") (class "Default")
      (node (ref "C14") (pin "1") (pinfunction "1_1") (pintype "passive"))
      (node (ref "C17") (pin "1") (pinfunction "1_1") (pintype "passive"))
      (node (ref "C3") (pin "2") (pinfunction "2_2") (pintype "passive"))
      (node (ref "C4") (pin "2") (pinfunction "2_2") (pintype "passive"))
      (node (ref "C5") (pin "2") (pinfunction "2_2") (pintype "passive"))
      (node (ref "C6") (pin "2") (pinfunction "2_2") (pintype "passive"))
      (node (ref "C7") (pin "2") (pinfunction "2_2") (pintype "passive"))
      (node (ref "C8") (pin "2") (pinfunction "2_2") (pintype "passive"))
      (node (ref "C9") (pin "2") (pinfunction "2_2") (pintype "passive"))
      (node (ref "JP5") (pin "1") (pinfunction "1_1") (pintype "passive"))
      (node (ref "JP5") (pin "2") (pinfunction "2_2") (pintype "passive"))
      (node (ref "K1") (pin "1") (pintype "passive"))
      (node (ref "R11") (pin "2") (pinfunction "2_2") (pintype "passive"))
      (node (ref "R16") (pin "2") (pinfunction "2_2") (pintype "passive"))
      (node (ref "R18") (pin "2") (pinfunction "2_2") (pintype "passive"))
      (node (ref "R2") (pin "1") (pinfunction "1_1") (pintype "passive"))
      (node (ref "R8") (pin "2") (pinfunction "2_2") (pintype "passive"))
      (node (ref "R9") (pin "1") (pinfunction "1_1") (pintype "passive"))
      (node (ref "RG1") (pin "1") (pinfunction "1_1") (pintype "passive"))
      (node (ref "RP1") (pin "1") (pinfunction "1_1") (pintype "passive"))
      (node (ref "SD1") (pin "4") (pinfunction "CDD_4") (pintype "passive"))
      (node (ref "U1") (pin "1") (pinfunction "IOVDD_1") (pintype "passive"))
      (node (ref "U1") (pin "10") (pinfunction "IOVDD_10") (pintype "passive"))
      (node (ref "U1") (pin "22") (pinfunction "IOVDD_22") (pintype "passive"))
      (node (ref "U1") (pin "23") (pinfunction "DVDD_23") (pintype "passive"))
      (node (ref "U1") (pin "33") (pinfunction "IOVDD_33") (pintype "passive"))
      (node (ref "U1") (pin "42") (pinfunction "IOVDD_42") (pintype "passive"))
      (node (ref "U1") (pin "43") (pinfunction "ADC_AVDD_43") (pintype "passive"))
      (node (ref "U1") (pin "44") (pinfunction "VREG_VIN_44") (pintype "passive"))
      (node (ref "U1") (pin "48") (pinfunction "USB_VDD_48") (pintype "passive"))
      (node (ref "U1") (pin "49") (pinfunction "IOVDD_49") (pintype "passive"))
      (node (ref "U2") (pin "8") (pinfunction "VCC_8") (pintype "power_in"))
      (node (ref "U3") (pin "2") (pinfunction "Vout_2") (pintype "passive"))
    )
    (net (code "65") (name "GND") (class "Default")
      (node (ref "C1") (pin "1") (pinfunction "1_1") (pintype "passive"))
      (node (ref "C10") (pin "1") (pinfunction "1_1") (pintype "passive"))
      (node (ref "C11") (pin "1") (pinfunction "1_1") (pintype "passive"))
      (node (ref "C12") (pin "1") (pinfunction "1_1") (pintype "passive"))
      (node (ref "C13") (pin "1") (pinfunction "1_1") (pintype "passive"))
      (node (ref "C14") (pin "2") (pinfunction "2_2") (pintype "passive"))
      (node (ref "C17") (pin "2") (pinfunction "2_2") (pintype "passive"))
      (node (ref "C18") (pin "1") (pinfunction "1_1") (pintype "passive"))
      (node (ref "C19") (pin "1") (pinfunction "1_1") (pintype "passive"))
      (node (ref "C2") (pin "1") (pinfunction "1_1") (pintype "passive"))
      (node (ref "C20") (pin "1") (pinfunction "1_1") (pintype "passive"))
      (node (ref "C21") (pin "1") (pinfunction "1_1") (pintype "passive"))
      (node (ref "C3") (pin "1") (pinfunction "1_1") (pintype "passive"))
      (node (ref "C4") (pin "1") (pinfunction "1_1") (pintype "passive"))
      (node (ref "C5") (pin "1") (pinfunction "1_1") (pintype "passive"))
      (node (ref "C6") (pin "1") (pinfunction "1_1") (pintype "passive"))
      (node (ref "C7") (pin "1") (pinfunction "1_1") (pintype "passive"))
      (node (ref "C8") (pin "1") (pinfunction "1_1") (pintype "passive"))
      (node (ref "C9") (pin "1") (pinfunction "1_1") (pintype "passive"))
      (node (ref "E1") (pin "2") (pinfunction "K_2") (pintype "passive"))
      (node (ref "E2") (pin "2") (pinfunction "K_2") (pintype "passive"))
      (node (ref "JP2") (pin "1") (pinfunction "1_1") (pintype "passive"))
      (node (ref "JP5") (pin "5") (pinfunction "5_5") (pintype "passive"))
      (node (ref "JP5") (pin "6") (pinfunction "6_6") (pintype "passive"))
      (node (ref "K2") (pin "2") (pintype "passive"))
      (node (ref "K3") (pin "1") (pintype "passive"))
      (node (ref "K4") (pin "1") (pintype "passive"))
      (node (ref "LED1") (pin "2") (pinfunction "K_2") (pintype "passive"))
      (node (ref "Q1") (pin "2") (pinfunction "E_2") (pintype "passive"))
      (node (ref "R1") (pin "1") (pinfunction "1_1") (pintype "passive"))
      (node (ref "R10") (pin "1") (pinfunction "1_1") (pintype "passive"))
      (node (ref "R13") (pin "1") (pinfunction "1_1") (pintype "passive"))
      (node (ref "R14") (pin "1") (pinfunction "1_1") (pintype "passive"))
      (node (ref "R17") (pin "1") (pinfunction "1_1") (pintype "passive"))
      (node (ref "R20") (pin "2") (pinfunction "2_2") (pintype "passive"))
      (node (ref "R24") (pin "1") (pinfunction "1_1") (pintype "passive"))
      (node (ref "R3") (pin "1") (pinfunction "1_1") (pintype "passive"))
      (node (ref "R5") (pin "1") (pinfunction "1_1") (pintype "passive"))
      (node (ref "R7") (pin "1") (pinfunction "1_1") (pintype "passive"))
      (node (ref "RP1") (pin "3") (pinfunction "3_3") (pintype "passive"))
      (node (ref "SD1") (pin "0") (pinfunction "GND_0") (pintype "passive"))
      (node (ref "SD1") (pin "6") (pinfunction "VSS_6") (pintype "passive"))
      (node (ref "TYPEC1") (pin "A12B1") (pinfunction "GND_A12B1") (pintype "passive"))
      (node (ref "TYPEC1") (pin "A1B12") (pinfunction "GND_A1B12") (pintype "passive"))
      (node (ref "U1") (pin "19") (pinfunction "TESTEN_19") (pintype "passive"))
      (node (ref "U1") (pin "57") (pinfunction "GND_57") (pintype "passive"))
      (node (ref "U2") (pin "4") (pinfunction "GND_4") (pintype "power_in"))
      (node (ref "U3") (pin "1") (pinfunction "GND_1") (pintype "passive"))
      (node (ref "U4") (pin "2") (pinfunction "S1_2") (pintype "passive"))
      (node (ref "U5") (pin "2") (pinfunction "S1_2") (pintype "passive"))
      (node (ref "ZR1") (pin "1") (pinfunction "1_1") (pintype "passive"))
      (node (ref "u6") (pin "7") (pinfunction "GND_7") (pintype "passive"))
      (node (ref "u6") (pin "9") (pinfunction "PAD_9") (pintype "passive"))
    )
    (net (code "66") (name "Net-(D1-K)") (class "Default")
      (node (ref "D1") (pin "2") (pinfunction "K_2") (pintype "passive"))
      (node (ref "Q2") (pin "S") (pinfunction "S_S") (pintype "passive"))
      (node (ref "S1") (pin "2") (pinfunction "2_2") (pintype "passive"))
      (node (ref "TP1") (pin "1") (pinfunction "1_1") (pintype "passive"))
    )
    (net (code "67") (name "Net-(D2-A)") (class "Default")
      (node (ref "D2") (pin "1") (pinfunction "A_1") (pintype "passive"))
      (node (ref "L1") (pin "1") (pinfunction "1_1") (pintype "passive"))
      (node (ref "u6") (pin "8") (pinfunction "LX_8") (pintype "passive"))
    )
    (net (code "68") (name "Net-(F1-Pad1)") (class "Default")
      (node (ref "F1") (pin "1") (pinfunction "1_1") (pintype "passive"))
      (node (ref "S1") (pin "1") (pinfunction "1_1") (pintype "passive"))
    )
    (net (code "69") (name "Net-(LED1-A)") (class "Default")
      (node (ref "LED1") (pin "1") (pinfunction "A_1") (pintype "passive"))
      (node (ref "R6") (pin "1") (pinfunction "1_1") (pintype "passive"))
    )
    (net (code "70") (name "Net-(LED2-K)") (class "Default")
      (node (ref "LED2") (pin "2") (pinfunction "K_2") (pintype "passive"))
      (node (ref "R13") (pin "2") (pinfunction "2_2") (pintype "passive"))
    )
    (net (code "71") (name "Net-(LED3-A)") (class "Default")
      (node (ref "LED3") (pin "1") (pinfunction "A_1") (pintype "passive"))
      (node (ref "LED4") (pin "1") (pinfunction "A_1") (pintype "passive"))
      (node (ref "R23") (pin "1") (pinfunction "1_1") (pintype "passive"))
    )
    (net (code "72") (name "Net-(LED3-K)") (class "Default")
      (node (ref "LED3") (pin "2") (pinfunction "K_2") (pintype "passive"))
      (node (ref "u6") (pin "2") (pinfunction "~{CHRG}_2") (pintype "passive"))
    )
    (net (code "73") (name "Net-(LED4-K)") (class "Default")
      (node (ref "LED4") (pin "2") (pinfunction "K_2") (pintype "passive"))
      (node (ref "u6") (pin "4") (pinfunction "~{STDBY}_4") (pintype "passive"))
    )
    (net (code "74") (name "Net-(Q1-B)") (class "Default")
      (node (ref "Q1") (pin "1") (pinfunction "B_1") (pintype "passive"))
      (node (ref "R4") (pin "2") (pinfunction "2_2") (pintype "passive"))
      (node (ref "R5") (pin "2") (pinfunction "2_2") (pintype "passive"))
    )
    (net (code "75") (name "Net-(Q1-C)") (class "Default")
      (node (ref "LS1") (pin "2") (pinfunction "2_2") (pintype "passive"))
      (node (ref "Q1") (pin "3") (pinfunction "C_3") (pintype "passive"))
    )
    (net (code "76") (name "Net-(TYPEC1-DN1)") (class "Default")
      (node (ref "R22") (pin "2") (pinfunction "2_2") (pintype "passive"))
      (node (ref "TYPEC1") (pin "A7") (pinfunction "DN1_A7") (pintype "passive"))
      (node (ref "TYPEC1") (pin "B7") (pinfunction "DN2_B7") (pintype "passive"))
    )
    (net (code "77") (name "Net-(TYPEC1-DP1)") (class "Default")
      (node (ref "R21") (pin "2") (pinfunction "2_2") (pintype "passive"))
      (node (ref "TYPEC1") (pin "A6") (pinfunction "DP1_A6") (pintype "passive"))
      (node (ref "TYPEC1") (pin "B6") (pinfunction "DP2_B6") (pintype "passive"))
    )
    (net (code "78") (name "Net-(U1-VREG_VOUT)") (class "Default")
      (node (ref "C1") (pin "2") (pinfunction "2_2") (pintype "passive"))
      (node (ref "C2") (pin "2") (pinfunction "2_2") (pintype "passive"))
      (node (ref "U1") (pin "45") (pinfunction "VREG_VOUT_45") (pintype "passive"))
      (node (ref "U1") (pin "50") (pinfunction "DVDD_50") (pintype "passive"))
    )
    (net (code "79") (name "Net-(U4-V-)") (class "Default")
      (node (ref "R14") (pin "2") (pinfunction "2_2") (pintype "passive"))
      (node (ref "U4") (pin "1") (pinfunction "V-_1") (pintype "passive"))
    )
    (net (code "80") (name "Net-(U4-VDD)") (class "Default")
      (node (ref "C15") (pin "1") (pinfunction "1_1") (pintype "passive"))
      (node (ref "R15") (pin "1") (pinfunction "1_1") (pintype "passive"))
      (node (ref "U4") (pin "5") (pinfunction "VDD_5") (pintype "passive"))
    )
    (net (code "81") (name "Net-(U5-V-)") (class "Default")
      (node (ref "R17") (pin "2") (pinfunction "2_2") (pintype "passive"))
      (node (ref "U5") (pin "1") (pinfunction "V-_1") (pintype "passive"))
    )
    (net (code "82") (name "Net-(U5-VDD)") (class "Default")
      (node (ref "C16") (pin "1") (pinfunction "1_1") (pintype "passive"))
      (node (ref "R19") (pin "1") (pinfunction "1_1") (pintype "passive"))
      (node (ref "U5") (pin "5") (pinfunction "VDD_5") (pintype "passive"))
    )
    (net (code "83") (name "Net-(u6-PROG)") (class "Default")
      (node (ref "R24") (pin "2") (pinfunction "2_2") (pintype "passive"))
      (node (ref "u6") (pin "3") (pinfunction "PROG_3") (pintype "passive"))
    )
    (net (code "84") (name "VBUS") (class "Default")
      (node (ref "C18") (pin "2") (pinfunction "2_2") (pintype "passive"))
      (node (ref "D1") (pin "1") (pinfunction "A_1") (pintype "passive"))
      (node (ref "Q2") (pin "G") (pinfunction "G_G") (pintype "passive"))
      (node (ref "R23") (pin "2") (pinfunction "2_2") (pintype "passive"))
      (node (ref "R7") (pin "2") (pinfunction "2_2") (pintype "passive"))
      (node (ref "TYPEC1") (pin "A4B9") (pinfunction "VBUS_A4B9") (pintype "passive"))
      (node (ref "TYPEC1") (pin "A9B4") (pinfunction "VBUS_A9B4") (pintype "passive"))
      (node (ref "u6") (pin "5") (pinfunction "VCC_5") (pintype "passive"))
    )
    (net (code "85") (name "unconnected-(S1-Pad3)") (class "Default")
      (node (ref "S1") (pin "3") (pinfunction "3_3") (pintype "passive+no_connect"))
    )
    (net (code "86") (name "unconnected-(SD1-CARD_DETECTION-Pad9)") (class "Default")
      (node (ref "SD1") (pin "9") (pinfunction "CARD_DETECTION_9") (pintype "passive+no_connect"))
    )
    (net (code "87") (name "unconnected-(TYPEC1-SBU1-PadA8)") (class "Default")
      (node (ref "TYPEC1") (pin "A8") (pinfunction "SBU1_A8") (pintype "passive+no_connect"))
    )
    (net (code "88") (name "unconnected-(TYPEC1-SBU2-PadB8)") (class "Default")
      (node (ref "TYPEC1") (pin "B8") (pinfunction "SBU2_B8") (pintype "passive+no_connect"))
    )
    (net (code "89") (name "unconnected-(TYPEC1-SHELL-Pad1)") (class "Default")
      (node (ref "TYPEC1") (pin "1") (pinfunction "SHELL_1") (pintype "passive+no_connect"))
    )
    (net (code "90") (name "unconnected-(TYPEC1-SHELL-Pad2)") (class "Default")
      (node (ref "TYPEC1") (pin "2") (pinfunction "SHELL_2") (pintype "passive+no_connect"))
    )
    (net (code "91") (name "unconnected-(TYPEC1-SHELL-Pad3)") (class "Default")
      (node (ref "TYPEC1") (pin "3") (pinfunction "SHELL_3") (pintype "passive+no_connect"))
    )
    (net (code "92") (name "unconnected-(TYPEC1-SHELL-Pad4)") (class "Default")
      (node (ref "TYPEC1") (pin "4") (pinfunction "SHELL_4") (pintype "passive+no_connect"))
    )
    (net (code "93") (name "unconnected-(U4-D-Pad4)") (class "Default")
      (node (ref "U4") (pin "4") (pinfunction "D_4") (pintype "passive+no_connect"))
    )
    (net (code "94") (name "unconnected-(U5-D-Pad4)") (class "Default")
      (node (ref "U5") (pin "4") (pinfunction "D_4") (pintype "passive+no_connect"))
    )
  )
)
